# sony_display_powersupply.net
KiCad netlist of a schematic drawn in EAGLE
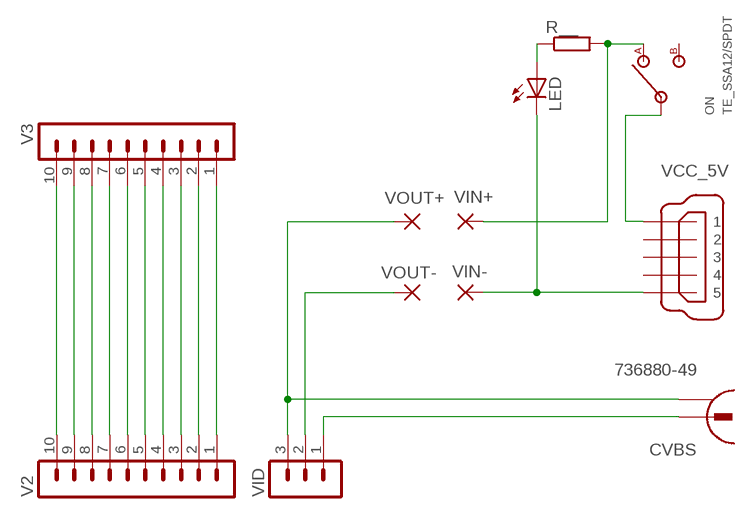
[diagram p0: schematic, sheet 1]

(export (version "E")
  (design (tool "Eeschema 10.0.6"))
  (components
    (comp (ref "CVBS")
      (value "736880-49")
      (footprint "eagle-import:736880-49")
      (libsource (lib "eagle-import") (part "736880-49"))
    )
    (comp (ref "LED")
      (value "LED3MM")
      (footprint "eagle-import:LED3MM")
      (libsource (lib "eagle-import") (part "LED3MM"))
    )
    (comp (ref "ON")
      (value "TE_SSA12/SPDT")
      (footprint "eagle-import:TE_SSA12_SPDT")
      (libsource (lib "eagle-import") (part "TE_SSA12/SPDT"))
    )
    (comp (ref "R__")
      (value "R-EU_M0805")
      (footprint "eagle-import:M0805")
      (libsource (lib "eagle-import") (part "R-EU_M0805"))
    )
    (comp (ref "V2")
      (value "MA10-1")
      (footprint "eagle-import:MA10-1")
      (libsource (lib "eagle-import") (part "MA10-1"))
    )
    (comp (ref "V3")
      (value "MA10-1")
      (footprint "eagle-import:MA10-1")
      (libsource (lib "eagle-import") (part "MA10-1"))
    )
    (comp (ref "VCC_5V")
      (value "MINI-USB-32005-301")
      (footprint "eagle-import:32005-301")
      (libsource (lib "eagle-import") (part "MINI-USB-32005-301"))
    )
    (comp (ref "VID")
      (value "MA03-1")
      (footprint "eagle-import:MA03-1")
      (libsource (lib "eagle-import") (part "MA03-1"))
    )
    (comp (ref "VIN+")
      (value "2,54/1,0")
      (footprint "eagle-import:2,54_1,0")
      (libsource (lib "eagle-import") (part "2,54/1,0"))
    )
    (comp (ref "VIN-")
      (value "2,54/1,0")
      (footprint "eagle-import:2,54_1,0")
      (libsource (lib "eagle-import") (part "2,54/1,0"))
    )
    (comp (ref "VOUT+")
      (value "2,54/1,0")
      (footprint "eagle-import:2,54_1,0")
      (libsource (lib "eagle-import") (part "2,54/1,0"))
    )
    (comp (ref "VOUT-")
      (value "2,54/1,0")
      (footprint "eagle-import:2,54_1,0")
      (libsource (lib "eagle-import") (part "2,54/1,0"))
    )
  )
  (nets
    (net (code "1") (name "Net-(CVBS-Pad1)") (class "Default")
      (node (ref "CVBS") (pin "1") (pinfunction "1_1") (pintype "passive"))
      (node (ref "VID") (pin "1") (pinfunction "1_1") (pintype "passive"))
    )
    (net (code "2") (name "Net-(LED-C)") (class "Default")
      (node (ref "LED") (pin "K") (pinfunction "C_K") (pintype "passive"))
      (node (ref "VCC_5V") (pin "5") (pinfunction "5_5") (pintype "passive"))
      (node (ref "VIN-") (pin "1") (pinfunction "P_1") (pintype "passive"))
    )
    (net (code "3") (name "Net-(LED-PadA)") (class "Default")
      (node (ref "LED") (pin "A") (pinfunction "A_A") (pintype "passive"))
      (node (ref "R__") (pin "1") (pinfunction "1_1") (pintype "passive"))
    )
    (net (code "4") (name "Net-(ON-A)") (class "Default")
      (node (ref "ON") (pin "1") (pinfunction "A_1") (pintype "bidirectional"))
      (node (ref "R__") (pin "2") (pinfunction "2_2") (pintype "passive"))
      (node (ref "VIN+") (pin "1") (pinfunction "P_1") (pintype "passive"))
    )
    (net (code "5") (name "Net-(ON-PadIN)") (class "Default")
      (node (ref "ON") (pin "IN") (pinfunction "IN_IN") (pintype "bidirectional"))
      (node (ref "VCC_5V") (pin "1") (pinfunction "1_1") (pintype "passive"))
    )
    (net (code "6") (name "Net-(V2-Pad1)") (class "Default")
      (node (ref "V2") (pin "1") (pinfunction "1_1") (pintype "passive"))
      (node (ref "V3") (pin "1") (pinfunction "1_1") (pintype "passive"))
    )
    (net (code "7") (name "Net-(V2-Pad2)") (class "Default")
      (node (ref "V2") (pin "2") (pinfunction "2_2") (pintype "passive"))
      (node (ref "V3") (pin "2") (pinfunction "2_2") (pintype "passive"))
    )
    (net (code "8") (name "Net-(V2-Pad3)") (class "Default")
      (node (ref "V2") (pin "3") (pinfunction "3_3") (pintype "passive"))
      (node (ref "V3") (pin "3") (pinfunction "3_3") (pintype "passive"))
    )
    (net (code "9") (name "Net-(V2-Pad4)") (class "Default")
      (node (ref "V2") (pin "4") (pinfunction "4_4") (pintype "passive"))
      (node (ref "V3") (pin "4") (pinfunction "4_4") (pintype "passive"))
    )
    (net (code "10") (name "Net-(V2-Pad5)") (class "Default")
      (node (ref "V2") (pin "5") (pinfunction "5_5") (pintype "passive"))
      (node (ref "V3") (pin "5") (pinfunction "5_5") (pintype "passive"))
    )
    (net (code "11") (name "Net-(V2-Pad6)") (class "Default")
      (node (ref "V2") (pin "6") (pinfunction "6_6") (pintype "passive"))
      (node (ref "V3") (pin "6") (pinfunction "6_6") (pintype "passive"))
    )
    (net (code "12") (name "Net-(V2-Pad7)") (class "Default")
      (node (ref "V2") (pin "7") (pinfunction "7_7") (pintype "passive"))
      (node (ref "V3") (pin "7") (pinfunction "7_7") (pintype "passive"))
    )
    (net (code "13") (name "Net-(V2-Pad8)") (class "Default")
      (node (ref "V2") (pin "8") (pinfunction "8_8") (pintype "passive"))
      (node (ref "V3") (pin "8") (pinfunction "8_8") (pintype "passive"))
    )
    (net (code "14") (name "Net-(V2-Pad9)") (class "Default")
      (node (ref "V2") (pin "9") (pinfunction "9_9") (pintype "passive"))
      (node (ref "V3") (pin "9") (pinfunction "9_9") (pintype "passive"))
    )
    (net (code "15") (name "Net-(V2-Pad10)") (class "Default")
      (node (ref "V2") (pin "10") (pinfunction "10_10") (pintype "passive"))
      (node (ref "V3") (pin "10") (pinfunction "10_10") (pintype "passive"))
    )
    (net (code "16") (name "Net-(VOUT+-P)") (class "Default")
      (node (ref "CVBS") (pin "2") (pinfunction "2_2") (pintype "passive"))
      (node (ref "VID") (pin "3") (pinfunction "3_3") (pintype "passive"))
      (node (ref "VOUT+") (pin "1") (pinfunction "P_1") (pintype "passive"))
    )
    (net (code "17") (name "Net-(VOUT--P)") (class "Default")
      (node (ref "VID") (pin "2") (pinfunction "2_2") (pintype "passive"))
      (node (ref "VOUT-") (pin "1") (pinfunction "P_1") (pintype "passive"))
    )
    (net (code "18") (name "unconnected-(CVBS-2-Pad2@2)") (class "Default")
      (node (ref "CVBS") (pin "2@2") (pinfunction "2_2@2") (pintype "passive"))
    )
    (net (code "19") (name "unconnected-(ON-B-Pad2)") (class "Default")
      (node (ref "ON") (pin "2") (pinfunction "B_2") (pintype "bidirectional"))
    )
    (net (code "20") (name "unconnected-(VCC_5V-Pad2)") (class "Default")
      (node (ref "VCC_5V") (pin "2") (pinfunction "2_2") (pintype "passive"))
    )
    (net (code "21") (name "unconnected-(VCC_5V-Pad3)") (class "Default")
      (node (ref "VCC_5V") (pin "3") (pinfunction "3_3") (pintype "passive"))
    )
    (net (code "22") (name "unconnected-(VCC_5V-Pad4)") (class "Default")
      (node (ref "VCC_5V") (pin "4") (pinfunction "4_4") (pintype "passive"))
    )
  )
)
